# AudioJackIO.net
KiCad netlist of a schematic drawn in EAGLE
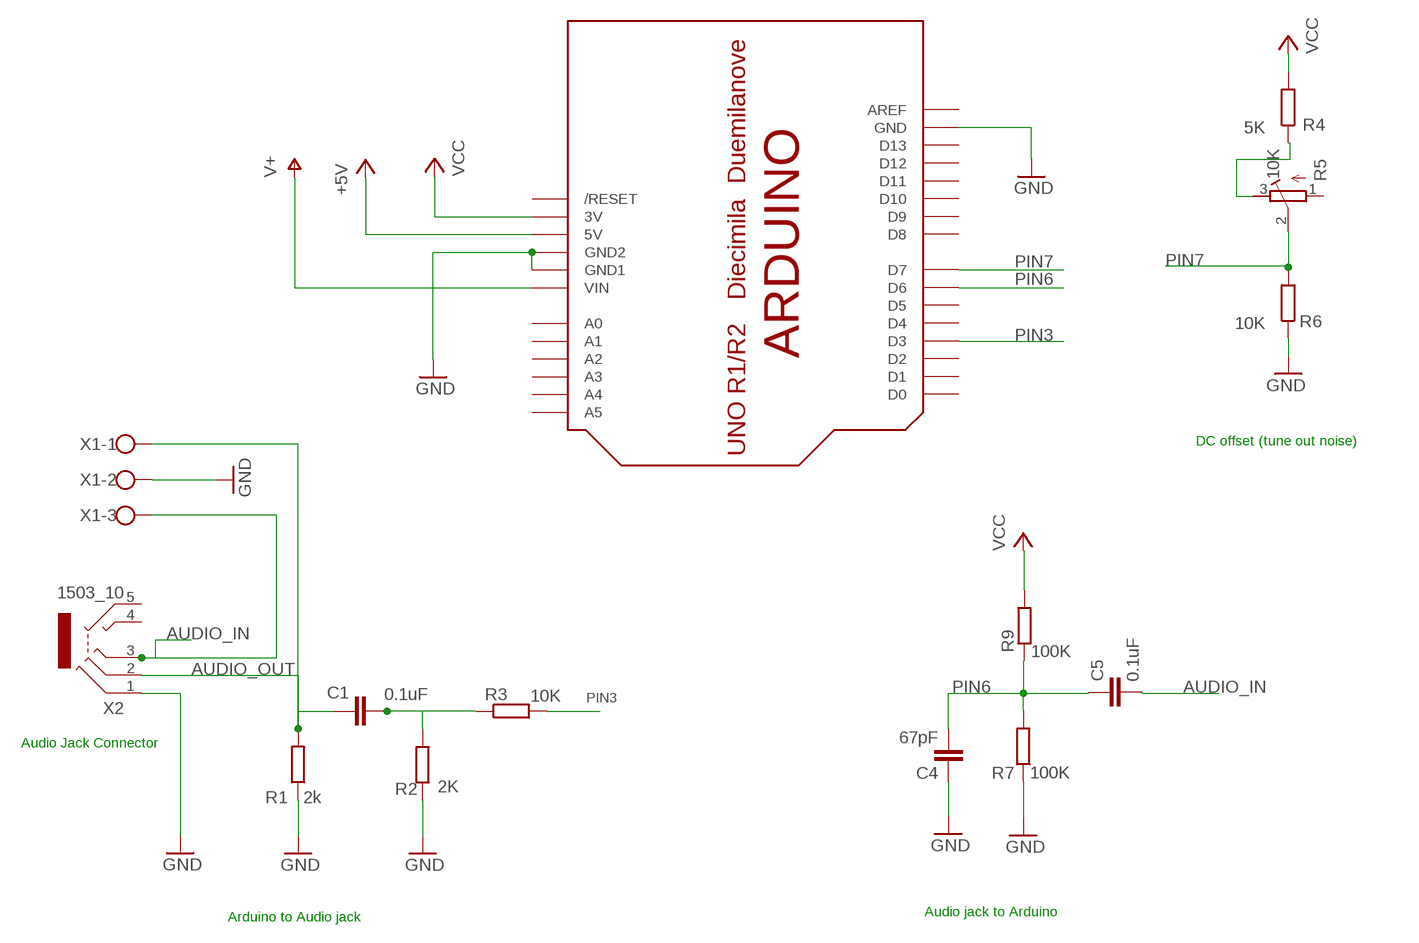
[diagram p0: schematic, sheet 1]

(export (version "E")
  (design (tool "Eeschema 10.0.6"))
  (components
    (comp (ref "C1")
      (value "0.1uF")
      (footprint "eagle-import:C025-025X050")
      (libsource (lib "eagle-import") (part "C-EU025-025X050"))
    )
    (comp (ref "C4")
      (value "67pF")
      (footprint "eagle-import:C025-025X050")
      (libsource (lib "eagle-import") (part "C-EU025-025X050"))
    )
    (comp (ref "C5")
      (value "0.1uF")
      (footprint "eagle-import:C025-025X050")
      (libsource (lib "eagle-import") (part "C-EU025-025X050"))
    )
    (comp (ref "R1")
      (value "2k")
      (footprint "eagle-import:0204_7")
      (libsource (lib "eagle-import") (part "R-EU_0204/7"))
    )
    (comp (ref "R2")
      (value "2K")
      (footprint "eagle-import:0204_7")
      (libsource (lib "eagle-import") (part "R-EU_0204/7"))
    )
    (comp (ref "R3")
      (value "10K")
      (footprint "eagle-import:0204_7")
      (libsource (lib "eagle-import") (part "R-EU_0204/7"))
    )
    (comp (ref "R4")
      (value "5K")
      (footprint "eagle-import:0204_7")
      (libsource (lib "eagle-import") (part "R-EU_0204/7"))
    )
    (comp (ref "R5")
      (value "10K")
      (footprint "eagle-import:RTRIM64Y")
      (libsource (lib "eagle-import") (part "R-TRIMM64Y"))
    )
    (comp (ref "R6")
      (value "10K")
      (footprint "eagle-import:0204_7")
      (libsource (lib "eagle-import") (part "R-EU_0204/7"))
    )
    (comp (ref "R7")
      (value "100K")
      (footprint "eagle-import:0204_7")
      (libsource (lib "eagle-import") (part "R-EU_0204/7"))
    )
    (comp (ref "R9")
      (value "100K")
      (footprint "eagle-import:0204_7")
      (libsource (lib "eagle-import") (part "R-EU_0204/7"))
    )
    (comp (ref "U$1")
      (value "ARDUINO-BPLACE")
      (footprint "eagle-import:ARDUINO-BPLACE")
      (libsource (lib "eagle-import") (part "ARDUINO-BPLACE"))
    )
    (comp (ref "X1")
      (value "W237-103")
      (footprint "eagle-import:W237-103")
      (fields (field (name "MPN") "237-103"))
      (libsource (lib "eagle-import") (part "W237-103"))
    )
    (comp (ref "X2")
      (value "1503_10")
      (footprint "eagle-import:1503_10")
      (libsource (lib "eagle-import") (part "1503_10"))
    )
  )
  (nets
    (net (code "1") (name "+5V") (class "Default")
      (node (ref "U$1") (pin "5V") (pinfunction "5V_5V") (pintype "power_in"))
    )
    (net (code "2") (name "/AUDIO_IN") (class "Default")
      (node (ref "C5") (pin "2") (pinfunction "2_2") (pintype "passive"))
      (node (ref "X1") (pin "3") (pinfunction "KL_3") (pintype "passive"))
      (node (ref "X2") (pin "3") (pinfunction "3_3") (pintype "passive"))
    )
    (net (code "3") (name "/AUDIO_OUT") (class "Default")
      (node (ref "C1") (pin "1") (pinfunction "1_1") (pintype "passive"))
      (node (ref "R1") (pin "2") (pinfunction "2_2") (pintype "passive"))
      (node (ref "X1") (pin "1") (pinfunction "KL_1") (pintype "passive"))
      (node (ref "X2") (pin "2") (pinfunction "2_2") (pintype "passive"))
    )
    (net (code "4") (name "/PIN3") (class "Default")
      (node (ref "R3") (pin "2") (pinfunction "2_2") (pintype "passive"))
      (node (ref "U$1") (pin "D3") (pinfunction "D3_D3") (pintype "bidirectional"))
    )
    (net (code "5") (name "/PIN6") (class "Default")
      (node (ref "C4") (pin "2") (pinfunction "2_2") (pintype "passive"))
      (node (ref "C5") (pin "1") (pinfunction "1_1") (pintype "passive"))
      (node (ref "R7") (pin "2") (pinfunction "2_2") (pintype "passive"))
      (node (ref "R9") (pin "1") (pinfunction "1_1") (pintype "passive"))
      (node (ref "U$1") (pin "D6") (pinfunction "D6_D6") (pintype "bidirectional"))
    )
    (net (code "6") (name "/PIN7") (class "Default")
      (node (ref "R5") (pin "2") (pinfunction "S_2") (pintype "passive"))
      (node (ref "R6") (pin "2") (pinfunction "2_2") (pintype "passive"))
      (node (ref "U$1") (pin "D7") (pinfunction "D7_D7") (pintype "bidirectional"))
    )
    (net (code "7") (name "GND") (class "Default")
      (node (ref "C4") (pin "1") (pinfunction "1_1") (pintype "passive"))
      (node (ref "R1") (pin "1") (pinfunction "1_1") (pintype "passive"))
      (node (ref "R2") (pin "2") (pinfunction "2_2") (pintype "passive"))
      (node (ref "R6") (pin "1") (pinfunction "1_1") (pintype "passive"))
      (node (ref "R7") (pin "1") (pinfunction "1_1") (pintype "passive"))
      (node (ref "U$1") (pin "GND") (pinfunction "GND_GND") (pintype "power_in"))
      (node (ref "U$1") (pin "GND1") (pinfunction "GND1_GND1") (pintype "power_in"))
      (node (ref "U$1") (pin "GND2") (pinfunction "GND2_GND2") (pintype "power_in"))
      (node (ref "X1") (pin "2") (pinfunction "KL_2") (pintype "passive"))
      (node (ref "X2") (pin "1") (pinfunction "1_1") (pintype "passive"))
    )
    (net (code "8") (name "Net-(C1-Pad2)") (class "Default")
      (node (ref "C1") (pin "2") (pinfunction "2_2") (pintype "passive"))
      (node (ref "R2") (pin "1") (pinfunction "1_1") (pintype "passive"))
      (node (ref "R3") (pin "1") (pinfunction "1_1") (pintype "passive"))
    )
    (net (code "9") (name "Net-(R5-E)") (class "Default")
      (node (ref "R4") (pin "1") (pinfunction "1_1") (pintype "passive"))
      (node (ref "R5") (pin "3") (pinfunction "E_3") (pintype "passive"))
    )
    (net (code "10") (name "V+") (class "Default")
      (node (ref "U$1") (pin "VIN") (pinfunction "VIN_VIN") (pintype "power_in"))
    )
    (net (code "11") (name "VCC") (class "Default")
      (node (ref "R4") (pin "2") (pinfunction "2_2") (pintype "passive"))
      (node (ref "R9") (pin "2") (pinfunction "2_2") (pintype "passive"))
      (node (ref "U$1") (pin "3V") (pinfunction "3V_3V") (pintype "power_in"))
    )
    (net (code "12") (name "unconnected-(R5-A-Pad1)") (class "Default")
      (node (ref "R5") (pin "1") (pinfunction "A_1") (pintype "passive"))
    )
    (net (code "13") (name "unconnected-(U$1-PadA0)") (class "Default")
      (node (ref "U$1") (pin "A0") (pinfunction "A0_A0") (pintype "bidirectional"))
    )
    (net (code "14") (name "unconnected-(U$1-PadA1)") (class "Default")
      (node (ref "U$1") (pin "A1") (pinfunction "A1_A1") (pintype "bidirectional"))
    )
    (net (code "15") (name "unconnected-(U$1-PadA2)") (class "Default")
      (node (ref "U$1") (pin "A2") (pinfunction "A2_A2") (pintype "bidirectional"))
    )
    (net (code "16") (name "unconnected-(U$1-PadA3)") (class "Default")
      (node (ref "U$1") (pin "A3") (pinfunction "A3_A3") (pintype "bidirectional"))
    )
    (net (code "17") (name "unconnected-(U$1-PadA4)") (class "Default")
      (node (ref "U$1") (pin "A4") (pinfunction "A4_A4") (pintype "bidirectional"))
    )
    (net (code "18") (name "unconnected-(U$1-PadA5)") (class "Default")
      (node (ref "U$1") (pin "A5") (pinfunction "A5_A5") (pintype "bidirectional"))
    )
    (net (code "19") (name "unconnected-(U$1-PadAREF)") (class "Default")
      (node (ref "U$1") (pin "AREF") (pinfunction "AREF_AREF") (pintype "bidirectional"))
    )
    (net (code "20") (name "unconnected-(U$1-PadD0)") (class "Default")
      (node (ref "U$1") (pin "D0") (pinfunction "D0_D0") (pintype "bidirectional"))
    )
    (net (code "21") (name "unconnected-(U$1-PadD1)") (class "Default")
      (node (ref "U$1") (pin "D1") (pinfunction "D1_D1") (pintype "bidirectional"))
    )
    (net (code "22") (name "unconnected-(U$1-PadD2)") (class "Default")
      (node (ref "U$1") (pin "D2") (pinfunction "D2_D2") (pintype "bidirectional"))
    )
    (net (code "23") (name "unconnected-(U$1-PadD4)") (class "Default")
      (node (ref "U$1") (pin "D4") (pinfunction "D4_D4") (pintype "bidirectional"))
    )
    (net (code "24") (name "unconnected-(U$1-PadD5)") (class "Default")
      (node (ref "U$1") (pin "D5") (pinfunction "D5_D5") (pintype "bidirectional"))
    )
    (net (code "25") (name "unconnected-(U$1-PadD8)") (class "Default")
      (node (ref "U$1") (pin "D8") (pinfunction "D8_D8") (pintype "bidirectional"))
    )
    (net (code "26") (name "unconnected-(U$1-PadD9)") (class "Default")
      (node (ref "U$1") (pin "D9") (pinfunction "D9_D9") (pintype "bidirectional"))
    )
    (net (code "27") (name "unconnected-(U$1-PadD10)") (class "Default")
      (node (ref "U$1") (pin "D10") (pinfunction "D10_D10") (pintype "bidirectional"))
    )
    (net (code "28") (name "unconnected-(U$1-PadD11)") (class "Default")
      (node (ref "U$1") (pin "D11") (pinfunction "D11_D11") (pintype "bidirectional"))
    )
    (net (code "29") (name "unconnected-(U$1-PadD12)") (class "Default")
      (node (ref "U$1") (pin "D12") (pinfunction "D12_D12") (pintype "bidirectional"))
    )
    (net (code "30") (name "unconnected-(U$1-PadD13)") (class "Default")
      (node (ref "U$1") (pin "D13") (pinfunction "D13_D13") (pintype "bidirectional"))
    )
    (net (code "31") (name "unconnected-(U$1-{slash}RESET-PadRESET)") (class "Default")
      (node (ref "U$1") (pin "RESET") (pinfunction "/RESET_RESET") (pintype "bidirectional"))
    )
    (net (code "32") (name "unconnected-(X2-Pad4)") (class "Default")
      (node (ref "X2") (pin "4") (pinfunction "4_4") (pintype "passive"))
    )
    (net (code "33") (name "unconnected-(X2-Pad5)") (class "Default")
      (node (ref "X2") (pin "5") (pinfunction "5_5") (pintype "passive"))
    )
  )
)
